# Location_controller.net
KiCad netlist of a schematic drawn in EAGLE
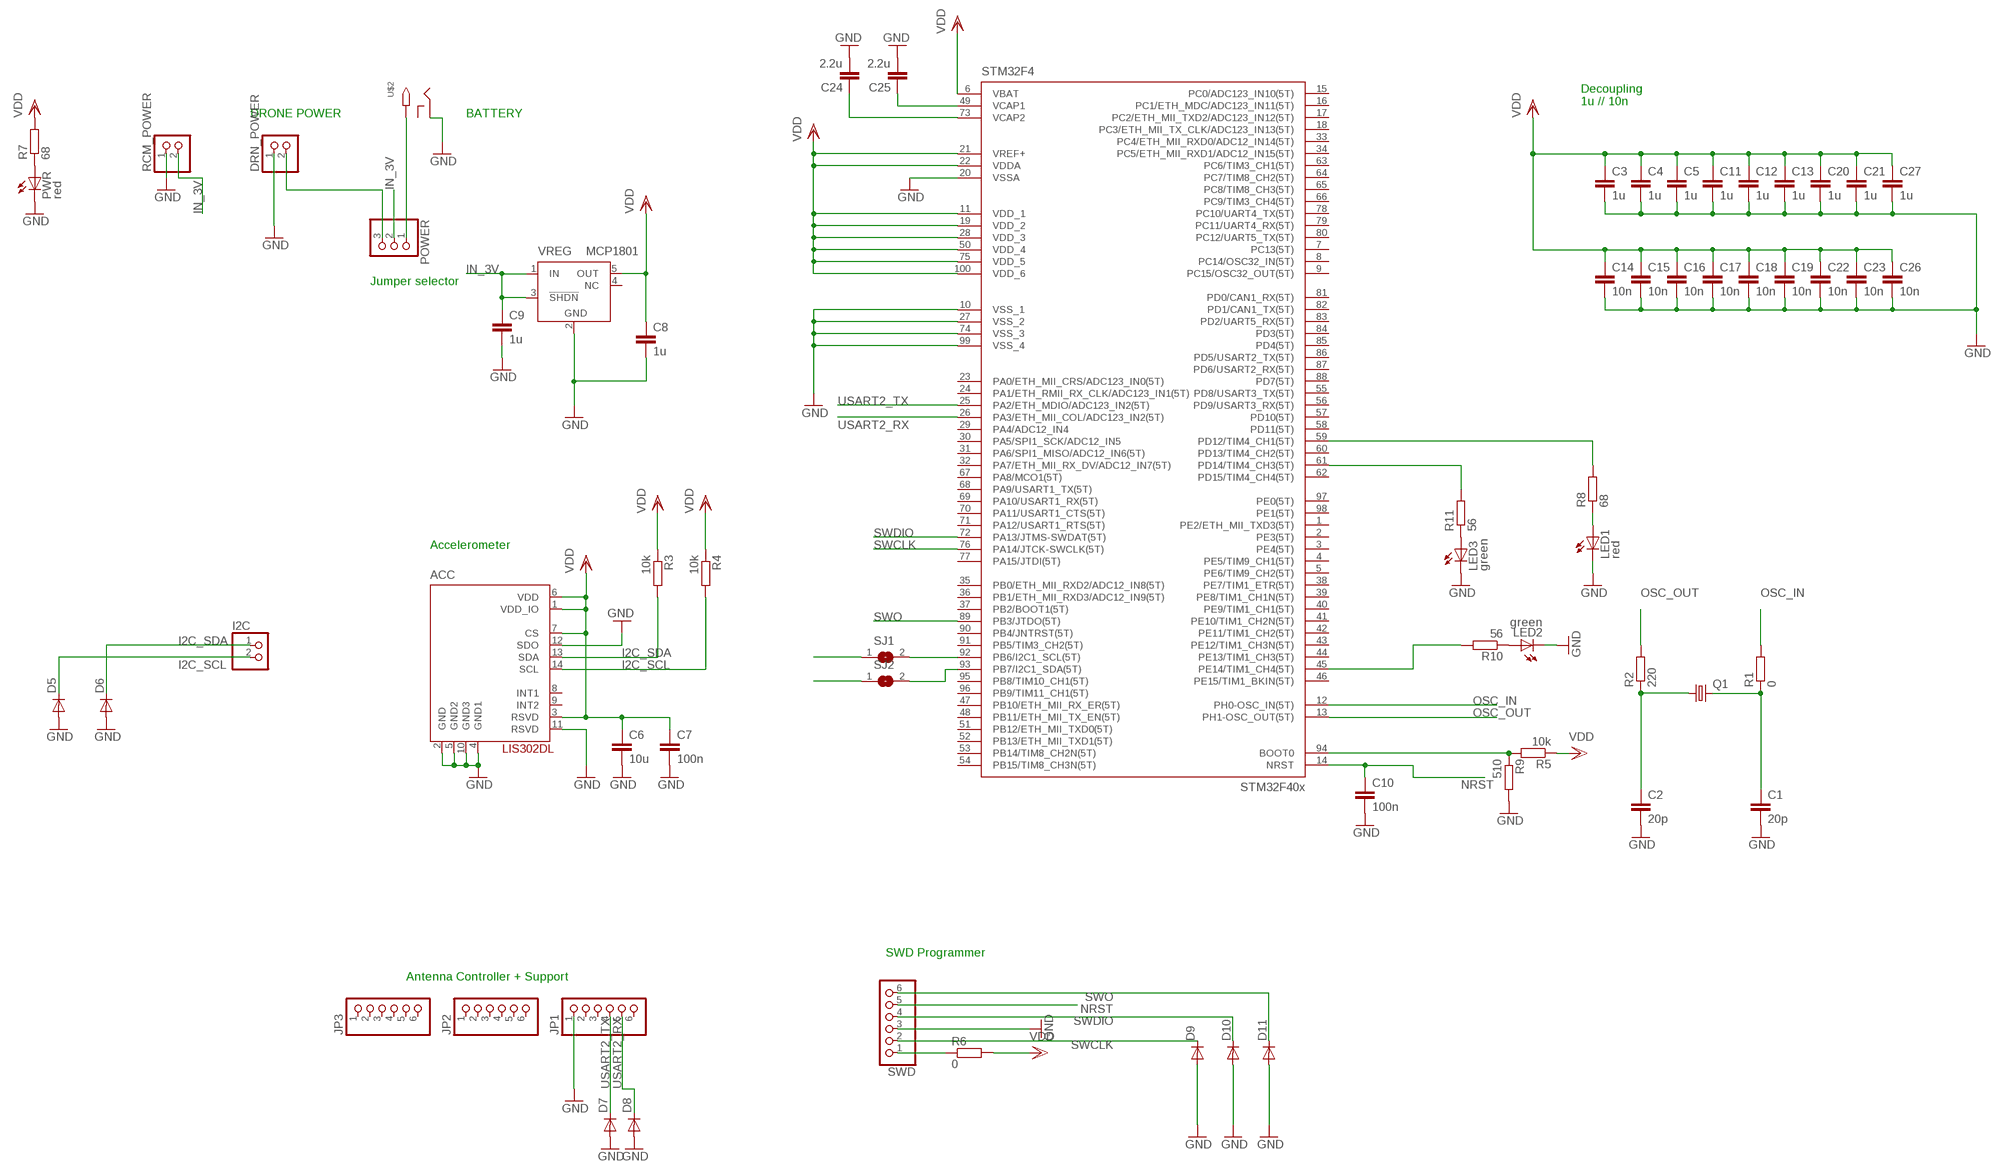
[diagram p0: schematic, sheet 1]

(export (version "E")
  (design (tool "Eeschema 10.0.6"))
  (components
    (comp (ref "ACC")
      (value "LIS302DL")
      (footprint "eagle-import:LGA-14")
      (libsource (lib "eagle-import") (part "LSM303DLHC"))
    )
    (comp (ref "C1")
      (value "20p")
      (footprint "eagle-import:C0805")
      (libsource (lib "eagle-import") (part "C"))
    )
    (comp (ref "C2")
      (value "20p")
      (footprint "eagle-import:C0805")
      (libsource (lib "eagle-import") (part "C"))
    )
    (comp (ref "C3")
      (value "1u")
      (footprint "eagle-import:C0805")
      (libsource (lib "eagle-import") (part "C"))
    )
    (comp (ref "C4")
      (value "1u")
      (footprint "eagle-import:C0805")
      (libsource (lib "eagle-import") (part "C"))
    )
    (comp (ref "C5")
      (value "1u")
      (footprint "eagle-import:C0805")
      (libsource (lib "eagle-import") (part "C"))
    )
    (comp (ref "C6")
      (value "10u")
      (footprint "eagle-import:C0805")
      (libsource (lib "eagle-import") (part "C"))
    )
    (comp (ref "C7")
      (value "100n")
      (footprint "eagle-import:C0805")
      (libsource (lib "eagle-import") (part "C"))
    )
    (comp (ref "C8")
      (value "1u")
      (footprint "eagle-import:C0805")
      (libsource (lib "eagle-import") (part "C"))
    )
    (comp (ref "C9")
      (value "1u")
      (footprint "eagle-import:C0805")
      (libsource (lib "eagle-import") (part "C"))
    )
    (comp (ref "C10")
      (value "100n")
      (footprint "eagle-import:C0805")
      (libsource (lib "eagle-import") (part "C"))
    )
    (comp (ref "C11")
      (value "1u")
      (footprint "eagle-import:C0805")
      (libsource (lib "eagle-import") (part "C"))
    )
    (comp (ref "C12")
      (value "1u")
      (footprint "eagle-import:C0805")
      (libsource (lib "eagle-import") (part "C"))
    )
    (comp (ref "C13")
      (value "1u")
      (footprint "eagle-import:C0805")
      (libsource (lib "eagle-import") (part "C"))
    )
    (comp (ref "C14")
      (value "10n")
      (footprint "eagle-import:C0805")
      (libsource (lib "eagle-import") (part "C"))
    )
    (comp (ref "C15")
      (value "10n")
      (footprint "eagle-import:C0805")
      (libsource (lib "eagle-import") (part "C"))
    )
    (comp (ref "C16")
      (value "10n")
      (footprint "eagle-import:C0805")
      (libsource (lib "eagle-import") (part "C"))
    )
    (comp (ref "C17")
      (value "10n")
      (footprint "eagle-import:C0805")
      (libsource (lib "eagle-import") (part "C"))
    )
    (comp (ref "C18")
      (value "10n")
      (footprint "eagle-import:C0805")
      (libsource (lib "eagle-import") (part "C"))
    )
    (comp (ref "C19")
      (value "10n")
      (footprint "eagle-import:C0805")
      (libsource (lib "eagle-import") (part "C"))
    )
    (comp (ref "C20")
      (value "1u")
      (footprint "eagle-import:C0805")
      (libsource (lib "eagle-import") (part "C"))
    )
    (comp (ref "C21")
      (value "1u")
      (footprint "eagle-import:C0805")
      (libsource (lib "eagle-import") (part "C"))
    )
    (comp (ref "C22")
      (value "10n")
      (footprint "eagle-import:C0805")
      (libsource (lib "eagle-import") (part "C"))
    )
    (comp (ref "C23")
      (value "10n")
      (footprint "eagle-import:C0805")
      (libsource (lib "eagle-import") (part "C"))
    )
    (comp (ref "C24")
      (value "2.2u")
      (footprint "eagle-import:C0805")
      (libsource (lib "eagle-import") (part "C"))
    )
    (comp (ref "C25")
      (value "2.2u")
      (footprint "eagle-import:C0805")
      (libsource (lib "eagle-import") (part "C"))
    )
    (comp (ref "C26")
      (value "10n")
      (footprint "eagle-import:C0805")
      (libsource (lib "eagle-import") (part "C"))
    )
    (comp (ref "C27")
      (value "1u")
      (footprint "eagle-import:C0805")
      (libsource (lib "eagle-import") (part "C"))
    )
    (comp (ref "D5")
      (value "DIODE-SOD523")
      (footprint "eagle-import:SOD523")
      (libsource (lib "eagle-import") (part "DIODE-SOD523"))
    )
    (comp (ref "D6")
      (value "DIODE-SOD523")
      (footprint "eagle-import:SOD523")
      (libsource (lib "eagle-import") (part "DIODE-SOD523"))
    )
    (comp (ref "D7")
      (value "DIODE-SOD523")
      (footprint "eagle-import:SOD523")
      (libsource (lib "eagle-import") (part "DIODE-SOD523"))
    )
    (comp (ref "D8")
      (value "DIODE-SOD523")
      (footprint "eagle-import:SOD523")
      (libsource (lib "eagle-import") (part "DIODE-SOD523"))
    )
    (comp (ref "D9")
      (value "DIODE-SOD523")
      (footprint "eagle-import:SOD523")
      (libsource (lib "eagle-import") (part "DIODE-SOD523"))
    )
    (comp (ref "D10")
      (value "DIODE-SOD523")
      (footprint "eagle-import:SOD523")
      (libsource (lib "eagle-import") (part "DIODE-SOD523"))
    )
    (comp (ref "D11")
      (value "DIODE-SOD523")
      (footprint "eagle-import:SOD523")
      (libsource (lib "eagle-import") (part "DIODE-SOD523"))
    )
    (comp (ref "DRN_POWER")
      (value "PINHD-1X2")
      (footprint "eagle-import:1X02")
      (libsource (lib "eagle-import") (part "PINHD-1X2"))
    )
    (comp (ref "I2C")
      (value "PINHD-1X2")
      (footprint "eagle-import:1X02")
      (libsource (lib "eagle-import") (part "PINHD-1X2"))
    )
    (comp (ref "JP1")
      (value "PINHD-1X6")
      (footprint "eagle-import:1X06")
      (libsource (lib "eagle-import") (part "PINHD-1X6"))
    )
    (comp (ref "JP2")
      (value "PINHD-1X6")
      (footprint "eagle-import:1X06")
      (libsource (lib "eagle-import") (part "PINHD-1X6"))
    )
    (comp (ref "JP3")
      (value "PINHD-1X6")
      (footprint "eagle-import:1X06")
      (libsource (lib "eagle-import") (part "PINHD-1X6"))
    )
    (comp (ref "LED1")
      (value "red")
      (footprint "eagle-import:CHIPLED_0805")
      (libsource (lib "eagle-import") (part "LEDCHIPLED_0805"))
    )
    (comp (ref "LED2")
      (value "green")
      (footprint "eagle-import:CHIPLED_0805")
      (libsource (lib "eagle-import") (part "LEDCHIPLED_0805"))
    )
    (comp (ref "LED3")
      (value "green")
      (footprint "eagle-import:CHIPLED_0805")
      (libsource (lib "eagle-import") (part "LEDCHIPLED_0805"))
    )
    (comp (ref "POWER")
      (value "PINHD-1X3")
      (footprint "eagle-import:1X03")
      (libsource (lib "eagle-import") (part "PINHD-1X3"))
    )
    (comp (ref "PWR")
      (value "red")
      (footprint "eagle-import:CHIPLED_0805")
      (libsource (lib "eagle-import") (part "LEDCHIPLED_0805"))
    )
    (comp (ref "Q1")
      (value "CRYSTALHC49S")
      (footprint "eagle-import:HC49_S")
      (libsource (lib "eagle-import") (part "CRYSTALHC49S"))
    )
    (comp (ref "R1") (value "0") (footprint "eagle-import:R0805") (libsource (lib "eagle-import") (part "R")))
    (comp (ref "R2")
      (value "220")
      (footprint "eagle-import:R0805")
      (libsource (lib "eagle-import") (part "R"))
    )
    (comp (ref "R3")
      (value "10k")
      (footprint "eagle-import:R0805")
      (libsource (lib "eagle-import") (part "R"))
    )
    (comp (ref "R4")
      (value "10k")
      (footprint "eagle-import:R0805")
      (libsource (lib "eagle-import") (part "R"))
    )
    (comp (ref "R5")
      (value "10k")
      (footprint "eagle-import:R0805")
      (libsource (lib "eagle-import") (part "R"))
    )
    (comp (ref "R6") (value "0") (footprint "eagle-import:R0805") (libsource (lib "eagle-import") (part "R")))
    (comp (ref "R7")
      (value "68")
      (footprint "eagle-import:R0805")
      (libsource (lib "eagle-import") (part "R"))
    )
    (comp (ref "R8")
      (value "68")
      (footprint "eagle-import:R0805")
      (libsource (lib "eagle-import") (part "R"))
    )
    (comp (ref "R9")
      (value "510")
      (footprint "eagle-import:R0805")
      (libsource (lib "eagle-import") (part "R"))
    )
    (comp (ref "R10")
      (value "56")
      (footprint "eagle-import:R0805")
      (libsource (lib "eagle-import") (part "R"))
    )
    (comp (ref "R11")
      (value "56")
      (footprint "eagle-import:R0805")
      (libsource (lib "eagle-import") (part "R"))
    )
    (comp (ref "RCM_POWER")
      (value "PINHD-1X2")
      (footprint "eagle-import:1X02")
      (libsource (lib "eagle-import") (part "PINHD-1X2"))
    )
    (comp (ref "SJ1") (value "SJ") (footprint "eagle-import:SJ") (libsource (lib "eagle-import") (part "SJ")))
    (comp (ref "SJ2") (value "SJ") (footprint "eagle-import:SJ") (libsource (lib "eagle-import") (part "SJ")))
    (comp (ref "STM32F4")
      (value "STM32F407V")
      (footprint "eagle-import:TQFP100")
      (libsource (lib "eagle-import") (part "STM32F407V"))
    )
    (comp (ref "SWD")
      (value "PINHD-1X6")
      (footprint "eagle-import:1X06")
      (libsource (lib "eagle-import") (part "PINHD-1X6"))
    )
    (comp (ref "U$2")
      (value "2.1MMJACKTHM")
      (footprint "eagle-import:PJ-102A")
      (libsource (lib "eagle-import") (part "2.1MMJACKTHM"))
    )
    (comp (ref "VREG")
      (value "MCP1801")
      (footprint "eagle-import:SOT23-5")
      (libsource (lib "eagle-import") (part "MCP1801"))
    )
  )
  (nets
    (net (code "1") (name "/I2C_SCL") (class "Default")
      (node (ref "ACC") (pin "14") (pinfunction "SCL_14") (pintype "bidirectional"))
      (node (ref "D5") (pin "C") (pinfunction "C_C") (pintype "passive"))
      (node (ref "I2C") (pin "2") (pinfunction "2_2") (pintype "passive"))
      (node (ref "R4") (pin "2") (pinfunction "2_2") (pintype "passive"))
      (node (ref "SJ1") (pin "1") (pinfunction "1_1") (pintype "passive"))
    )
    (net (code "2") (name "/I2C_SDA") (class "Default")
      (node (ref "ACC") (pin "13") (pinfunction "SDA_13") (pintype "bidirectional"))
      (node (ref "D6") (pin "C") (pinfunction "C_C") (pintype "passive"))
      (node (ref "I2C") (pin "1") (pinfunction "1_1") (pintype "passive"))
      (node (ref "R3") (pin "2") (pinfunction "2_2") (pintype "passive"))
      (node (ref "SJ2") (pin "1") (pinfunction "1_1") (pintype "passive"))
    )
    (net (code "3") (name "/IN_3V") (class "Default")
      (node (ref "C9") (pin "1") (pinfunction "1_1") (pintype "passive"))
      (node (ref "POWER") (pin "2") (pinfunction "2_2") (pintype "passive"))
      (node (ref "RCM_POWER") (pin "2") (pinfunction "2_2") (pintype "passive"))
      (node (ref "VREG") (pin "1") (pinfunction "IN_1") (pintype "input"))
      (node (ref "VREG") (pin "3") (pinfunction "~{SHDN}_3") (pintype "input"))
    )
    (net (code "4") (name "/NRST") (class "Default")
      (node (ref "C10") (pin "1") (pinfunction "1_1") (pintype "passive"))
      (node (ref "STM32F4") (pin "14") (pinfunction "NRST_14") (pintype "bidirectional"))
      (node (ref "SWD") (pin "5") (pinfunction "5_5") (pintype "passive"))
    )
    (net (code "5") (name "/OSC_IN") (class "Default")
      (node (ref "R1") (pin "2") (pinfunction "2_2") (pintype "passive"))
      (node (ref "STM32F4") (pin "12") (pinfunction "PH0-OSC_IN(5T)_12") (pintype "bidirectional"))
    )
    (net (code "6") (name "/OSC_OUT") (class "Default")
      (node (ref "R2") (pin "2") (pinfunction "2_2") (pintype "passive"))
      (node (ref "STM32F4") (pin "13") (pinfunction "PH1-OSC_OUT(5T)_13") (pintype "bidirectional"))
    )
    (net (code "7") (name "/SWCLK") (class "Default")
      (node (ref "D9") (pin "C") (pinfunction "C_C") (pintype "passive"))
      (node (ref "STM32F4") (pin "76") (pinfunction "PA14/JTCK-SWCLK(5T)_76") (pintype "bidirectional"))
      (node (ref "SWD") (pin "2") (pinfunction "2_2") (pintype "passive"))
    )
    (net (code "8") (name "/SWDIO") (class "Default")
      (node (ref "D10") (pin "C") (pinfunction "C_C") (pintype "passive"))
      (node (ref "STM32F4") (pin "72") (pinfunction "PA13/JTMS-SWDAT(5T)_72") (pintype "bidirectional"))
      (node (ref "SWD") (pin "4") (pinfunction "4_4") (pintype "passive"))
    )
    (net (code "9") (name "/SWO") (class "Default")
      (node (ref "D11") (pin "C") (pinfunction "C_C") (pintype "passive"))
      (node (ref "STM32F4") (pin "89") (pinfunction "PB3/JTDO(5T)_89") (pintype "bidirectional"))
      (node (ref "SWD") (pin "6") (pinfunction "6_6") (pintype "passive"))
    )
    (net (code "10") (name "/USART2_RX") (class "Default")
      (node (ref "D8") (pin "C") (pinfunction "C_C") (pintype "passive"))
      (node (ref "JP1") (pin "5") (pinfunction "5_5") (pintype "passive"))
      (node (ref "STM32F4") (pin "26") (pinfunction "PA3/ETH_MII_COL/ADC123_IN2(5T)_26") (pintype "bidirectional"))
    )
    (net (code "11") (name "/USART2_TX") (class "Default")
      (node (ref "D7") (pin "C") (pinfunction "C_C") (pintype "passive"))
      (node (ref "JP1") (pin "4") (pinfunction "4_4") (pintype "passive"))
      (node (ref "STM32F4") (pin "25") (pinfunction "PA2/ETH_MDIO/ADC123_IN2(5T)_25") (pintype "bidirectional"))
    )
    (net (code "12") (name "GND") (class "Default")
      (node (ref "ACC") (pin "10") (pinfunction "GND3_10") (pintype "passive"))
      (node (ref "ACC") (pin "11") (pinfunction "RSVD_11") (pintype "passive"))
      (node (ref "ACC") (pin "12") (pinfunction "SDO_12") (pintype "passive"))
      (node (ref "ACC") (pin "2") (pinfunction "GND_2") (pintype "power_in"))
      (node (ref "ACC") (pin "4") (pinfunction "GND1_4") (pintype "passive"))
      (node (ref "ACC") (pin "5") (pinfunction "GND2_5") (pintype "passive"))
      (node (ref "C1") (pin "2") (pinfunction "2_2") (pintype "passive"))
      (node (ref "C10") (pin "2") (pinfunction "2_2") (pintype "passive"))
      (node (ref "C11") (pin "2") (pinfunction "2_2") (pintype "passive"))
      (node (ref "C12") (pin "2") (pinfunction "2_2") (pintype "passive"))
      (node (ref "C13") (pin "2") (pinfunction "2_2") (pintype "passive"))
      (node (ref "C14") (pin "2") (pinfunction "2_2") (pintype "passive"))
      (node (ref "C15") (pin "2") (pinfunction "2_2") (pintype "passive"))
      (node (ref "C16") (pin "2") (pinfunction "2_2") (pintype "passive"))
      (node (ref "C17") (pin "2") (pinfunction "2_2") (pintype "passive"))
      (node (ref "C18") (pin "2") (pinfunction "2_2") (pintype "passive"))
      (node (ref "C19") (pin "2") (pinfunction "2_2") (pintype "passive"))
      (node (ref "C2") (pin "2") (pinfunction "2_2") (pintype "passive"))
      (node (ref "C20") (pin "2") (pinfunction "2_2") (pintype "passive"))
      (node (ref "C21") (pin "2") (pinfunction "2_2") (pintype "passive"))
      (node (ref "C22") (pin "2") (pinfunction "2_2") (pintype "passive"))
      (node (ref "C23") (pin "2") (pinfunction "2_2") (pintype "passive"))
      (node (ref "C24") (pin "2") (pinfunction "2_2") (pintype "passive"))
      (node (ref "C25") (pin "2") (pinfunction "2_2") (pintype "passive"))
      (node (ref "C26") (pin "2") (pinfunction "2_2") (pintype "passive"))
      (node (ref "C27") (pin "2") (pinfunction "2_2") (pintype "passive"))
      (node (ref "C3") (pin "2") (pinfunction "2_2") (pintype "passive"))
      (node (ref "C4") (pin "2") (pinfunction "2_2") (pintype "passive"))
      (node (ref "C5") (pin "2") (pinfunction "2_2") (pintype "passive"))
      (node (ref "C6") (pin "2") (pinfunction "2_2") (pintype "passive"))
      (node (ref "C7") (pin "2") (pinfunction "2_2") (pintype "passive"))
      (node (ref "C8") (pin "2") (pinfunction "2_2") (pintype "passive"))
      (node (ref "C9") (pin "2") (pinfunction "2_2") (pintype "passive"))
      (node (ref "D10") (pin "A") (pinfunction "A_A") (pintype "passive"))
      (node (ref "D11") (pin "A") (pinfunction "A_A") (pintype "passive"))
      (node (ref "D5") (pin "A") (pinfunction "A_A") (pintype "passive"))
      (node (ref "D6") (pin "A") (pinfunction "A_A") (pintype "passive"))
      (node (ref "D7") (pin "A") (pinfunction "A_A") (pintype "passive"))
      (node (ref "D8") (pin "A") (pinfunction "A_A") (pintype "passive"))
      (node (ref "D9") (pin "A") (pinfunction "A_A") (pintype "passive"))
      (node (ref "DRN_POWER") (pin "1") (pinfunction "1_1") (pintype "passive"))
      (node (ref "JP1") (pin "1") (pinfunction "1_1") (pintype "passive"))
      (node (ref "LED1") (pin "C") (pinfunction "C_C") (pintype "passive"))
      (node (ref "LED2") (pin "C") (pinfunction "C_C") (pintype "passive"))
      (node (ref "LED3") (pin "C") (pinfunction "C_C") (pintype "passive"))
      (node (ref "PWR") (pin "C") (pinfunction "C_C") (pintype "passive"))
      (node (ref "R9") (pin "2") (pinfunction "2_2") (pintype "passive"))
      (node (ref "RCM_POWER") (pin "1") (pinfunction "1_1") (pintype "passive"))
      (node (ref "STM32F4") (pin "10") (pinfunction "VSS_1_10") (pintype "bidirectional"))
      (node (ref "STM32F4") (pin "20") (pinfunction "VSSA_20") (pintype "bidirectional"))
      (node (ref "STM32F4") (pin "27") (pinfunction "VSS_2_27") (pintype "bidirectional"))
      (node (ref "STM32F4") (pin "74") (pinfunction "VSS_3_74") (pintype "bidirectional"))
      (node (ref "STM32F4") (pin "99") (pinfunction "VSS_4_99") (pintype "bidirectional"))
      (node (ref "SWD") (pin "3") (pinfunction "3_3") (pintype "passive"))
      (node (ref "U$2") (pin "RING") (pinfunction "RING_RING") (pintype "bidirectional"))
      (node (ref "VREG") (pin "2") (pinfunction "GND_2") (pintype "power_in"))
    )
    (net (code "13") (name "Net-(C1-Pad1)") (class "Default")
      (node (ref "C1") (pin "1") (pinfunction "1_1") (pintype "passive"))
      (node (ref "Q1") (pin "2") (pinfunction "2_2") (pintype "passive"))
      (node (ref "R1") (pin "1") (pinfunction "1_1") (pintype "passive"))
    )
    (net (code "14") (name "Net-(C2-Pad1)") (class "Default")
      (node (ref "C2") (pin "1") (pinfunction "1_1") (pintype "passive"))
      (node (ref "Q1") (pin "1") (pinfunction "1_1") (pintype "passive"))
      (node (ref "R2") (pin "1") (pinfunction "1_1") (pintype "passive"))
    )
    (net (code "15") (name "Net-(DRN_POWER-Pad2)") (class "Default")
      (node (ref "DRN_POWER") (pin "2") (pinfunction "2_2") (pintype "passive"))
      (node (ref "POWER") (pin "3") (pinfunction "3_3") (pintype "passive"))
    )
    (net (code "16") (name "Net-(LED1-PadA)") (class "Default")
      (node (ref "LED1") (pin "A") (pinfunction "A_A") (pintype "passive"))
      (node (ref "R8") (pin "1") (pinfunction "1_1") (pintype "passive"))
    )
    (net (code "17") (name "Net-(LED2-PadA)") (class "Default")
      (node (ref "LED2") (pin "A") (pinfunction "A_A") (pintype "passive"))
      (node (ref "R10") (pin "1") (pinfunction "1_1") (pintype "passive"))
    )
    (net (code "18") (name "Net-(LED3-PadA)") (class "Default")
      (node (ref "LED3") (pin "A") (pinfunction "A_A") (pintype "passive"))
      (node (ref "R11") (pin "1") (pinfunction "1_1") (pintype "passive"))
    )
    (net (code "19") (name "Net-(POWER-Pad1)") (class "Default")
      (node (ref "POWER") (pin "1") (pinfunction "1_1") (pintype "passive"))
      (node (ref "U$2") (pin "TIP") (pinfunction "TIP_TIP") (pintype "bidirectional"))
    )
    (net (code "20") (name "Net-(PWR-PadA)") (class "Default")
      (node (ref "PWR") (pin "A") (pinfunction "A_A") (pintype "passive"))
      (node (ref "R7") (pin "1") (pinfunction "1_1") (pintype "passive"))
    )
    (net (code "21") (name "Net-(R6-Pad1)") (class "Default")
      (node (ref "R6") (pin "1") (pinfunction "1_1") (pintype "passive"))
      (node (ref "SWD") (pin "1") (pinfunction "1_1") (pintype "passive"))
    )
    (net (code "22") (name "Net-(STM32F4-BOOT0)") (class "Default")
      (node (ref "R5") (pin "2") (pinfunction "2_2") (pintype "passive"))
      (node (ref "R9") (pin "1") (pinfunction "1_1") (pintype "passive"))
      (node (ref "STM32F4") (pin "94") (pinfunction "BOOT0_94") (pintype "bidirectional"))
    )
    (net (code "23") (name "Net-(STM32F4-PB6{slash}I2C1_SCL(5T))") (class "Default")
      (node (ref "SJ1") (pin "2") (pinfunction "2_2") (pintype "passive"))
      (node (ref "STM32F4") (pin "92") (pinfunction "PB6/I2C1_SCL(5T)_92") (pintype "bidirectional"))
    )
    (net (code "24") (name "Net-(STM32F4-PB7{slash}I2C1_SDA(5T))") (class "Default")
      (node (ref "SJ2") (pin "2") (pinfunction "2_2") (pintype "passive"))
      (node (ref "STM32F4") (pin "93") (pinfunction "PB7/I2C1_SDA(5T)_93") (pintype "bidirectional"))
    )
    (net (code "25") (name "Net-(STM32F4-PD12{slash}TIM4_CH1(5T))") (class "Default")
      (node (ref "R8") (pin "2") (pinfunction "2_2") (pintype "passive"))
      (node (ref "STM32F4") (pin "59") (pinfunction "PD12/TIM4_CH1(5T)_59") (pintype "bidirectional"))
    )
    (net (code "26") (name "Net-(STM32F4-PD14{slash}TIM4_CH3(5T))") (class "Default")
      (node (ref "R11") (pin "2") (pinfunction "2_2") (pintype "passive"))
      (node (ref "STM32F4") (pin "61") (pinfunction "PD14/TIM4_CH3(5T)_61") (pintype "bidirectional"))
    )
    (net (code "27") (name "Net-(STM32F4-PE14{slash}TIM1_CH4(5T))") (class "Default")
      (node (ref "R10") (pin "2") (pinfunction "2_2") (pintype "passive"))
      (node (ref "STM32F4") (pin "45") (pinfunction "PE14/TIM1_CH4(5T)_45") (pintype "bidirectional"))
    )
    (net (code "28") (name "Net-(STM32F4-VCAP1)") (class "Default")
      (node (ref "C25") (pin "1") (pinfunction "1_1") (pintype "passive"))
      (node (ref "STM32F4") (pin "49") (pinfunction "VCAP1_49") (pintype "bidirectional"))
    )
    (net (code "29") (name "Net-(STM32F4-VCAP2)") (class "Default")
      (node (ref "C24") (pin "1") (pinfunction "1_1") (pintype "passive"))
      (node (ref "STM32F4") (pin "73") (pinfunction "VCAP2_73") (pintype "bidirectional"))
    )
    (net (code "30") (name "VDD") (class "Default")
      (node (ref "ACC") (pin "1") (pinfunction "VDD_IO_1") (pintype "power_in"))
      (node (ref "ACC") (pin "3") (pinfunction "RSVD_3") (pintype "passive"))
      (node (ref "ACC") (pin "6") (pinfunction "VDD_6") (pintype "power_in"))
      (node (ref "ACC") (pin "7") (pinfunction "CS_7") (pintype "bidirectional"))
      (node (ref "C11") (pin "1") (pinfunction "1_1") (pintype "passive"))
      (node (ref "C12") (pin "1") (pinfunction "1_1") (pintype "passive"))
      (node (ref "C13") (pin "1") (pinfunction "1_1") (pintype "passive"))
      (node (ref "C14") (pin "1") (pinfunction "1_1") (pintype "passive"))
      (node (ref "C15") (pin "1") (pinfunction "1_1") (pintype "passive"))
      (node (ref "C16") (pin "1") (pinfunction "1_1") (pintype "passive"))
      (node (ref "C17") (pin "1") (pinfunction "1_1") (pintype "passive"))
      (node (ref "C18") (pin "1") (pinfunction "1_1") (pintype "passive"))
      (node (ref "C19") (pin "1") (pinfunction "1_1") (pintype "passive"))
      (node (ref "C20") (pin "1") (pinfunction "1_1") (pintype "passive"))
      (node (ref "C21") (pin "1") (pinfunction "1_1") (pintype "passive"))
      (node (ref "C22") (pin "1") (pinfunction "1_1") (pintype "passive"))
      (node (ref "C23") (pin "1") (pinfunction "1_1") (pintype "passive"))
      (node (ref "C26") (pin "1") (pinfunction "1_1") (pintype "passive"))
      (node (ref "C27") (pin "1") (pinfunction "1_1") (pintype "passive"))
      (node (ref "C3") (pin "1") (pinfunction "1_1") (pintype "passive"))
      (node (ref "C4") (pin "1") (pinfunction "1_1") (pintype "passive"))
      (node (ref "C5") (pin "1") (pinfunction "1_1") (pintype "passive"))
      (node (ref "C6") (pin "1") (pinfunction "1_1") (pintype "passive"))
      (node (ref "C7") (pin "1") (pinfunction "1_1") (pintype "passive"))
      (node (ref "C8") (pin "1") (pinfunction "1_1") (pintype "passive"))
      (node (ref "R3") (pin "1") (pinfunction "1_1") (pintype "passive"))
      (node (ref "R4") (pin "1") (pinfunction "1_1") (pintype "passive"))
      (node (ref "R5") (pin "1") (pinfunction "1_1") (pintype "passive"))
      (node (ref "R6") (pin "2") (pinfunction "2_2") (pintype "passive"))
      (node (ref "R7") (pin "2") (pinfunction "2_2") (pintype "passive"))
      (node (ref "STM32F4") (pin "100") (pinfunction "VDD_6_100") (pintype "bidirectional"))
      (node (ref "STM32F4") (pin "11") (pinfunction "VDD_1_11") (pintype "bidirectional"))
      (node (ref "STM32F4") (pin "19") (pinfunction "VDD_2_19") (pintype "bidirectional"))
      (node (ref "STM32F4") (pin "21") (pinfunction "VREF+_21") (pintype "bidirectional"))
      (node (ref "STM32F4") (pin "22") (pinfunction "VDDA_22") (pintype "bidirectional"))
      (node (ref "STM32F4") (pin "28") (pinfunction "VDD_3_28") (pintype "bidirectional"))
      (node (ref "STM32F4") (pin "50") (pinfunction "VDD_4_50") (pintype "bidirectional"))
      (node (ref "STM32F4") (pin "6") (pinfunction "VBAT_6") (pintype "bidirectional"))
      (node (ref "STM32F4") (pin "75") (pinfunction "VDD_5_75") (pintype "bidirectional"))
      (node (ref "VREG") (pin "5") (pinfunction "OUT_5") (pintype "output"))
    )
    (net (code "31") (name "unconnected-(ACC-INT1-Pad8)") (class "Default")
      (node (ref "ACC") (pin "8") (pinfunction "INT1_8") (pintype "bidirectional"))
    )
    (net (code "32") (name "unconnected-(ACC-INT2-Pad9)") (class "Default")
      (node (ref "ACC") (pin "9") (pinfunction "INT2_9") (pintype "bidirectional"))
    )
    (net (code "33") (name "unconnected-(JP1-Pad2)") (class "Default")
      (node (ref "JP1") (pin "2") (pinfunction "2_2") (pintype "passive"))
    )
    (net (code "34") (name "unconnected-(JP1-Pad3)") (class "Default")
      (node (ref "JP1") (pin "3") (pinfunction "3_3") (pintype "passive"))
    )
    (net (code "35") (name "unconnected-(JP1-Pad6)") (class "Default")
      (node (ref "JP1") (pin "6") (pinfunction "6_6") (pintype "passive"))
    )
    (net (code "36") (name "unconnected-(JP2-Pad1)") (class "Default")
      (node (ref "JP2") (pin "1") (pinfunction "1_1") (pintype "passive"))
    )
    (net (code "37") (name "unconnected-(JP2-Pad2)") (class "Default")
      (node (ref "JP2") (pin "2") (pinfunction "2_2") (pintype "passive"))
    )
    (net (code "38") (name "unconnected-(JP2-Pad3)") (class "Default")
      (node (ref "JP2") (pin "3") (pinfunction "3_3") (pintype "passive"))
    )
    (net (code "39") (name "unconnected-(JP2-Pad4)") (class "Default")
      (node (ref "JP2") (pin "4") (pinfunction "4_4") (pintype "passive"))
    )
    (net (code "40") (name "unconnected-(JP2-Pad5)") (class "Default")
      (node (ref "JP2") (pin "5") (pinfunction "5_5") (pintype "passive"))
    )
    (net (code "41") (name "unconnected-(JP2-Pad6)") (class "Default")
      (node (ref "JP2") (pin "6") (pinfunction "6_6") (pintype "passive"))
    )
    (net (code "42") (name "unconnected-(JP3-Pad1)") (class "Default")
      (node (ref "JP3") (pin "1") (pinfunction "1_1") (pintype "passive"))
    )
    (net (code "43") (name "unconnected-(JP3-Pad2)") (class "Default")
      (node (ref "JP3") (pin "2") (pinfunction "2_2") (pintype "passive"))
    )
    (net (code "44") (name "unconnected-(JP3-Pad3)") (class "Default")
      (node (ref "JP3") (pin "3") (pinfunction "3_3") (pintype "passive"))
    )
    (net (code "45") (name "unconnected-(JP3-Pad4)") (class "Default")
      (node (ref "JP3") (pin "4") (pinfunction "4_4") (pintype "passive"))
    )
    (net (code "46") (name "unconnected-(JP3-Pad5)") (class "Default")
      (node (ref "JP3") (pin "5") (pinfunction "5_5") (pintype "passive"))
    )
    (net (code "47") (name "unconnected-(JP3-Pad6)") (class "Default")
      (node (ref "JP3") (pin "6") (pinfunction "6_6") (pintype "passive"))
    )
    (net (code "48") (name "unconnected-(STM32F4-PA0{slash}ETH_MII_CRS{slash}ADC123_IN0(5T)-Pad23)") (class "Default")
      (node (ref "STM32F4") (pin "23") (pinfunction "PA0/ETH_MII_CRS/ADC123_IN0(5T)_23") (pintype "bidirectional"))
    )
    (net (code "49") (name "unconnected-(STM32F4-PA1{slash}ETH_RMII_RX_CLK{slash}ADC123_IN1(5T)-Pad24)") (class "Default")
      (node (ref "STM32F4") (pin "24") (pinfunction "PA1/ETH_RMII_RX_CLK/ADC123_IN1(5T)_24") (pintype "bidirectional"))
    )
    (net (code "50") (name "unconnected-(STM32F4-PA4{slash}ADC12_IN4-Pad29)") (class "Default")
      (node (ref "STM32F4") (pin "29") (pinfunction "PA4/ADC12_IN4_29") (pintype "bidirectional"))
    )
    (net (code "51") (name "unconnected-(STM32F4-PA5{slash}SPI1_SCK{slash}ADC12_IN5-Pad30)") (class "Default")
      (node (ref "STM32F4") (pin "30") (pinfunction "PA5/SPI1_SCK/ADC12_IN5_30") (pintype "bidirectional"))
    )
    (net (code "52") (name "unconnected-(STM32F4-PA6{slash}SPI1_MISO{slash}ADC12_IN6(5T)-Pad31)") (class "Default")
      (node (ref "STM32F4") (pin "31") (pinfunction "PA6/SPI1_MISO/ADC12_IN6(5T)_31") (pintype "bidirectional"))
    )
    (net (code "53") (name "unconnected-(STM32F4-PA7{slash}ETH_MII_RX_DV{slash}ADC12_IN7(5T)-Pad32)") (class "Default")
      (node (ref "STM32F4") (pin "32") (pinfunction "PA7/ETH_MII_RX_DV/ADC12_IN7(5T)_32") (pintype "bidirectional"))
    )
    (net (code "54") (name "unconnected-(STM32F4-PA8{slash}MCO1(5T)-Pad67)") (class "Default")
      (node (ref "STM32F4") (pin "67") (pinfunction "PA8/MCO1(5T)_67") (pintype "bidirectional"))
    )
    (net (code "55") (name "unconnected-(STM32F4-PA9{slash}USART1_TX(5T)-Pad68)") (class "Default")
      (node (ref "STM32F4") (pin "68") (pinfunction "PA9/USART1_TX(5T)_68") (pintype "bidirectional"))
    )
    (net (code "56") (name "unconnected-(STM32F4-PA10{slash}USART1_RX(5T)-Pad69)") (class "Default")
      (node (ref "STM32F4") (pin "69") (pinfunction "PA10/USART1_RX(5T)_69") (pintype "bidirectional"))
    )
    (net (code "57") (name "unconnected-(STM32F4-PA11{slash}USART1_CTS(5T)-Pad70)") (class "Default")
      (node (ref "STM32F4") (pin "70") (pinfunction "PA11/USART1_CTS(5T)_70") (pintype "bidirectional"))
    )
    (net (code "58") (name "unconnected-(STM32F4-PA12{slash}USART1_RTS(5T)-Pad71)") (class "Default")
      (node (ref "STM32F4") (pin "71") (pinfunction "PA12/USART1_RTS(5T)_71") (pintype "bidirectional"))
    )
    (net (code "59") (name "unconnected-(STM32F4-PA15{slash}JTDI(5T)-Pad77)") (class "Default")
      (node (ref "STM32F4") (pin "77") (pinfunction "PA15/JTDI(5T)_77") (pintype "bidirectional"))
    )
    (net (code "60") (name "unconnected-(STM32F4-PB0{slash}ETH_MII_RXD2{slash}ADC12_IN8(5T)-Pad35)") (class "Default")
      (node (ref "STM32F4") (pin "35") (pinfunction "PB0/ETH_MII_RXD2/ADC12_IN8(5T)_35") (pintype "bidirectional"))
    )
    (net (code "61") (name "unconnected-(STM32F4-PB1{slash}ETH_MII_RXD3{slash}ADC12_IN9(5T)-Pad36)") (class "Default")
      (node (ref "STM32F4") (pin "36") (pinfunction "PB1/ETH_MII_RXD3/ADC12_IN9(5T)_36") (pintype "bidirectional"))
    )
    (net (code "62") (name "unconnected-(STM32F4-PB2{slash}BOOT1(5T)-Pad37)") (class "Default")
      (node (ref "STM32F4") (pin "37") (pinfunction "PB2/BOOT1(5T)_37") (pintype "bidirectional"))
    )
    (net (code "63") (name "unconnected-(STM32F4-PB4{slash}JNTRST(5T)-Pad90)") (class "Default")
      (node (ref "STM32F4") (pin "90") (pinfunction "PB4/JNTRST(5T)_90") (pintype "bidirectional"))
    )
    (net (code "64") (name "unconnected-(STM32F4-PB5{slash}TIM3_CH2(5T)-Pad91)") (class "Default")
      (node (ref "STM32F4") (pin "91") (pinfunction "PB5/TIM3_CH2(5T)_91") (pintype "bidirectional"))
    )
    (net (code "65") (name "unconnected-(STM32F4-PB8{slash}TIM10_CH1(5T)-Pad95)") (class "Default")
      (node (ref "STM32F4") (pin "95") (pinfunction "PB8/TIM10_CH1(5T)_95") (pintype "bidirectional"))
    )
    (net (code "66") (name "unconnected-(STM32F4-PB9{slash}TIM11_CH1(5T)-Pad96)") (class "Default")
      (node (ref "STM32F4") (pin "96") (pinfunction "PB9/TIM11_CH1(5T)_96") (pintype "bidirectional"))
    )
    (net (code "67") (name "unconnected-(STM32F4-PB10{slash}ETH_MII_RX_ER(5T)-Pad47)") (class "Default")
      (node (ref "STM32F4") (pin "47") (pinfunction "PB10/ETH_MII_RX_ER(5T)_47") (pintype "bidirectional"))
    )
    (net (code "68") (name "unconnected-(STM32F4-PB11{slash}ETH_MII_TX_EN(5T)-Pad48)") (class "Default")
      (node (ref "STM32F4") (pin "48") (pinfunction "PB11/ETH_MII_TX_EN(5T)_48") (pintype "bidirectional"))
    )
    (net (code "69") (name "unconnected-(STM32F4-PB12{slash}ETH_MII_TXD0(5T)-Pad51)") (class "Default")
      (node (ref "STM32F4") (pin "51") (pinfunction "PB12/ETH_MII_TXD0(5T)_51") (pintype "bidirectional"))
    )
    (net (code "70") (name "unconnected-(STM32F4-PB13{slash}ETH_MII_TXD1(5T)-Pad52)") (class "Default")
      (node (ref "STM32F4") (pin "52") (pinfunction "PB13/ETH_MII_TXD1(5T)_52") (pintype "bidirectional"))
    )
    (net (code "71") (name "unconnected-(STM32F4-PB14{slash}TIM8_CH2N(5T)-Pad53)") (class "Default")
      (node (ref "STM32F4") (pin "53") (pinfunction "PB14/TIM8_CH2N(5T)_53") (pintype "bidirectional"))
    )
    (net (code "72") (name "unconnected-(STM32F4-PB15{slash}TIM8_CH3N(5T)-Pad54)") (class "Default")
      (node (ref "STM32F4") (pin "54") (pinfunction "PB15/TIM8_CH3N(5T)_54") (pintype "bidirectional"))
    )
    (net (code "73") (name "unconnected-(STM32F4-PC0{slash}ADC123_IN10(5T)-Pad15)") (class "Default")
      (node (ref "STM32F4") (pin "15") (pinfunction "PC0/ADC123_IN10(5T)_15") (pintype "bidirectional"))
    )
    (net (code "74") (name "unconnected-(STM32F4-PC1{slash}ETH_MDC{slash}ADC123_IN11(5T)-Pad16)") (class "Default")
      (node (ref "STM32F4") (pin "16") (pinfunction "PC1/ETH_MDC/ADC123_IN11(5T)_16") (pintype "bidirectional"))
    )
    (net (code "75") (name "unconnected-(STM32F4-PC2{slash}ETH_MII_TXD2{slash}ADC123_IN12(5T)-Pad17)") (class "Default")
      (node (ref "STM32F4") (pin "17") (pinfunction "PC2/ETH_MII_TXD2/ADC123_IN12(5T)_17") (pintype "bidirectional"))
    )
    (net (code "76") (name "unconnected-(STM32F4-PC3{slash}ETH_MII_TX_CLK{slash}ADC123_IN13(5T)-Pad18)") (class "Default")
      (node (ref "STM32F4") (pin "18") (pinfunction "PC3/ETH_MII_TX_CLK/ADC123_IN13(5T)_18") (pintype "bidirectional"))
    )
    (net (code "77") (name "unconnected-(STM32F4-PC4{slash}ETH_MII_RXD0{slash}ADC12_IN14(5T)-Pad33)") (class "Default")
      (node (ref "STM32F4") (pin "33") (pinfunction "PC4/ETH_MII_RXD0/ADC12_IN14(5T)_33") (pintype "bidirectional"))
    )
    (net (code "78") (name "unconnected-(STM32F4-PC5{slash}ETH_MII_RXD1{slash}ADC12_IN15(5T)-Pad34)") (class "Default")
      (node (ref "STM32F4") (pin "34") (pinfunction "PC5/ETH_MII_RXD1/ADC12_IN15(5T)_34") (pintype "bidirectional"))
    )
    (net (code "79") (name "unconnected-(STM32F4-PC6{slash}TIM3_CH1(5T)-Pad63)") (class "Default")
      (node (ref "STM32F4") (pin "63") (pinfunction "PC6/TIM3_CH1(5T)_63") (pintype "bidirectional"))
    )
    (net (code "80") (name "unconnected-(STM32F4-PC7{slash}TIM8_CH2(5T)-Pad64)") (class "Default")
      (node (ref "STM32F4") (pin "64") (pinfunction "PC7/TIM8_CH2(5T)_64") (pintype "bidirectional"))
    )
    (net (code "81") (name "unconnected-(STM32F4-PC8{slash}TIM8_CH3(5T)-Pad65)") (class "Default")
      (node (ref "STM32F4") (pin "65") (pinfunction "PC8/TIM8_CH3(5T)_65") (pintype "bidirectional"))
    )
    (net (code "82") (name "unconnected-(STM32F4-PC9{slash}TIM3_CH4(5T)-Pad66)") (class "Default")
      (node (ref "STM32F4") (pin "66") (pinfunction "PC9/TIM3_CH4(5T)_66") (pintype "bidirectional"))
    )
    (net (code "83") (name "unconnected-(STM32F4-PC10{slash}UART4_TX(5T)-Pad78)") (class "Default")
      (node (ref "STM32F4") (pin "78") (pinfunction "PC10/UART4_TX(5T)_78") (pintype "bidirectional"))
    )
    (net (code "84") (name "unconnected-(STM32F4-PC11{slash}UART4_RX(5T)-Pad79)") (class "Default")
      (node (ref "STM32F4") (pin "79") (pinfunction "PC11/UART4_RX(5T)_79") (pintype "bidirectional"))
    )
    (net (code "85") (name "unconnected-(STM32F4-PC12{slash}UART5_TX(5T)-Pad80)") (class "Default")
      (node (ref "STM32F4") (pin "80") (pinfunction "PC12/UART5_TX(5T)_80") (pintype "bidirectional"))
    )
    (net (code "86") (name "unconnected-(STM32F4-PC13(5T)-Pad7)") (class "Default")
      (node (ref "STM32F4") (pin "7") (pinfunction "PC13(5T)_7") (pintype "bidirectional"))
    )
    (net (code "87") (name "unconnected-(STM32F4-PC14{slash}OSC32_IN(5T)-Pad8)") (class "Default")
      (node (ref "STM32F4") (pin "8") (pinfunction "PC14/OSC32_IN(5T)_8") (pintype "bidirectional"))
    )
    (net (code "88") (name "unconnected-(STM32F4-PC15{slash}OSC32_OUT(5T)-Pad9)") (class "Default")
      (node (ref "STM32F4") (pin "9") (pinfunction "PC15/OSC32_OUT(5T)_9") (pintype "bidirectional"))
    )
    (net (code "89") (name "unconnected-(STM32F4-PD0{slash}CAN1_RX(5T)-Pad81)") (class "Default")
      (node (ref "STM32F4") (pin "81") (pinfunction "PD0/CAN1_RX(5T)_81") (pintype "bidirectional"))
    )
    (net (code "90") (name "unconnected-(STM32F4-PD1{slash}CAN1_TX(5T)-Pad82)") (class "Default")
      (node (ref "STM32F4") (pin "82") (pinfunction "PD1/CAN1_TX(5T)_82") (pintype "bidirectional"))
    )
    (net (code "91") (name "unconnected-(STM32F4-PD2{slash}UART5_RX(5T)-Pad83)") (class "Default")
      (node (ref "STM32F4") (pin "83") (pinfunction "PD2/UART5_RX(5T)_83") (pintype "bidirectional"))
    )
    (net (code "92") (name "unconnected-(STM32F4-PD3(5T)-Pad84)") (class "Default")
      (node (ref "STM32F4") (pin "84") (pinfunction "PD3(5T)_84") (pintype "bidirectional"))
    )
    (net (code "93") (name "unconnected-(STM32F4-PD4(5T)-Pad85)") (class "Default")
      (node (ref "STM32F4") (pin "85") (pinfunction "PD4(5T)_85") (pintype "bidirectional"))
    )
    (net (code "94") (name "unconnected-(STM32F4-PD5{slash}USART2_TX(5T)-Pad86)") (class "Default")
      (node (ref "STM32F4") (pin "86") (pinfunction "PD5/USART2_TX(5T)_86") (pintype "bidirectional"))
    )
    (net (code "95") (name "unconnected-(STM32F4-PD6{slash}USART2_RX(5T)-Pad87)") (class "Default")
      (node (ref "STM32F4") (pin "87") (pinfunction "PD6/USART2_RX(5T)_87") (pintype "bidirectional"))
    )
    (net (code "96") (name "unconnected-(STM32F4-PD7(5T)-Pad88)") (class "Default")
      (node (ref "STM32F4") (pin "88") (pinfunction "PD7(5T)_88") (pintype "bidirectional"))
    )
    (net (code "97") (name "unconnected-(STM32F4-PD8{slash}USART3_TX(5T)-Pad55)") (class "Default")
      (node (ref "STM32F4") (pin "55") (pinfunction "PD8/USART3_TX(5T)_55") (pintype "bidirectional"))
    )
    (net (code "98") (name "unconnected-(STM32F4-PD9{slash}USART3_RX(5T)-Pad56)") (class "Default")
      (node (ref "STM32F4") (pin "56") (pinfunction "PD9/USART3_RX(5T)_56") (pintype "bidirectional"))
    )
    (net (code "99") (name "unconnected-(STM32F4-PD10(5T)-Pad57)") (class "Default")
      (node (ref "STM32F4") (pin "57") (pinfunction "PD10(5T)_57") (pintype "bidirectional"))
    )
    (net (code "100") (name "unconnected-(STM32F4-PD11(5T)-Pad58)") (class "Default")
      (node (ref "STM32F4") (pin "58") (pinfunction "PD11(5T)_58") (pintype "bidirectional"))
    )
    (net (code "101") (name "unconnected-(STM32F4-PD13{slash}TIM4_CH2(5T)-Pad60)") (class "Default")
      (node (ref "STM32F4") (pin "60") (pinfunction "PD13/TIM4_CH2(5T)_60") (pintype "bidirectional"))
    )
    (net (code "102") (name "unconnected-(STM32F4-PD15{slash}TIM4_CH4(5T)-Pad62)") (class "Default")
      (node (ref "STM32F4") (pin "62") (pinfunction "PD15/TIM4_CH4(5T)_62") (pintype "bidirectional"))
    )
    (net (code "103") (name "unconnected-(STM32F4-PE0(5T)-Pad97)") (class "Default")
      (node (ref "STM32F4") (pin "97") (pinfunction "PE0(5T)_97") (pintype "bidirectional"))
    )
    (net (code "104") (name "unconnected-(STM32F4-PE1(5T)-Pad98)") (class "Default")
      (node (ref "STM32F4") (pin "98") (pinfunction "PE1(5T)_98") (pintype "bidirectional"))
    )
    (net (code "105") (name "unconnected-(STM32F4-PE2{slash}ETH_MII_TXD3(5T)-Pad1)") (class "Default")
      (node (ref "STM32F4") (pin "1") (pinfunction "PE2/ETH_MII_TXD3(5T)_1") (pintype "bidirectional"))
    )
    (net (code "106") (name "unconnected-(STM32F4-PE3(5T)-Pad2)") (class "Default")
      (node (ref "STM32F4") (pin "2") (pinfunction "PE3(5T)_2") (pintype "bidirectional"))
    )
    (net (code "107") (name "unconnected-(STM32F4-PE4(5T)-Pad3)") (class "Default")
      (node (ref "STM32F4") (pin "3") (pinfunction "PE4(5T)_3") (pintype "bidirectional"))
    )
    (net (code "108") (name "unconnected-(STM32F4-PE5{slash}TIM9_CH1(5T)-Pad4)") (class "Default")
      (node (ref "STM32F4") (pin "4") (pinfunction "PE5/TIM9_CH1(5T)_4") (pintype "bidirectional"))
    )
    (net (code "109") (name "unconnected-(STM32F4-PE6{slash}TIM9_CH2(5T)-Pad5)") (class "Default")
      (node (ref "STM32F4") (pin "5") (pinfunction "PE6/TIM9_CH2(5T)_5") (pintype "bidirectional"))
    )
    (net (code "110") (name "unconnected-(STM32F4-PE7{slash}TIM1_ETR(5T)-Pad38)") (class "Default")
      (node (ref "STM32F4") (pin "38") (pinfunction "PE7/TIM1_ETR(5T)_38") (pintype "bidirectional"))
    )
    (net (code "111") (name "unconnected-(STM32F4-PE8{slash}TIM1_CH1N(5T)-Pad39)") (class "Default")
      (node (ref "STM32F4") (pin "39") (pinfunction "PE8/TIM1_CH1N(5T)_39") (pintype "bidirectional"))
    )
    (net (code "112") (name "unconnected-(STM32F4-PE9{slash}TIM1_CH1(5T)-Pad40)") (class "Default")
      (node (ref "STM32F4") (pin "40") (pinfunction "PE9/TIM1_CH1(5T)_40") (pintype "bidirectional"))
    )
    (net (code "113") (name "unconnected-(STM32F4-PE10{slash}TIM1_CH2N(5T)-Pad41)") (class "Default")
      (node (ref "STM32F4") (pin "41") (pinfunction "PE10/TIM1_CH2N(5T)_41") (pintype "bidirectional"))
    )
    (net (code "114") (name "unconnected-(STM32F4-PE11{slash}TIM1_CH2(5T)-Pad42)") (class "Default")
      (node (ref "STM32F4") (pin "42") (pinfunction "PE11/TIM1_CH2(5T)_42") (pintype "bidirectional"))
    )
    (net (code "115") (name "unconnected-(STM32F4-PE12{slash}TIM1_CH3N(5T)-Pad43)") (class "Default")
      (node (ref "STM32F4") (pin "43") (pinfunction "PE12/TIM1_CH3N(5T)_43") (pintype "bidirectional"))
    )
    (net (code "116") (name "unconnected-(STM32F4-PE13{slash}TIM1_CH3(5T)-Pad44)") (class "Default")
      (node (ref "STM32F4") (pin "44") (pinfunction "PE13/TIM1_CH3(5T)_44") (pintype "bidirectional"))
    )
    (net (code "117") (name "unconnected-(STM32F4-PE15{slash}TIM1_BKIN(5T)-Pad46)") (class "Default")
      (node (ref "STM32F4") (pin "46") (pinfunction "PE15/TIM1_BKIN(5T)_46") (pintype "bidirectional"))
    )
    (net (code "118") (name "unconnected-(U$2-PadRING_SW)") (class "Default")
      (node (ref "U$2") (pin "RING_SW") (pinfunction "RING_SW_RING_SW") (pintype "bidirectional"))
    )
    (net (code "119") (name "unconnected-(VREG-NC-Pad4)") (class "Default")
      (node (ref "VREG") (pin "4") (pinfunction "NC_4") (pintype "input"))
    )
  )
)
